# 8_USB_Hub.net
KiCad netlist of a schematic drawn in Altium Designer
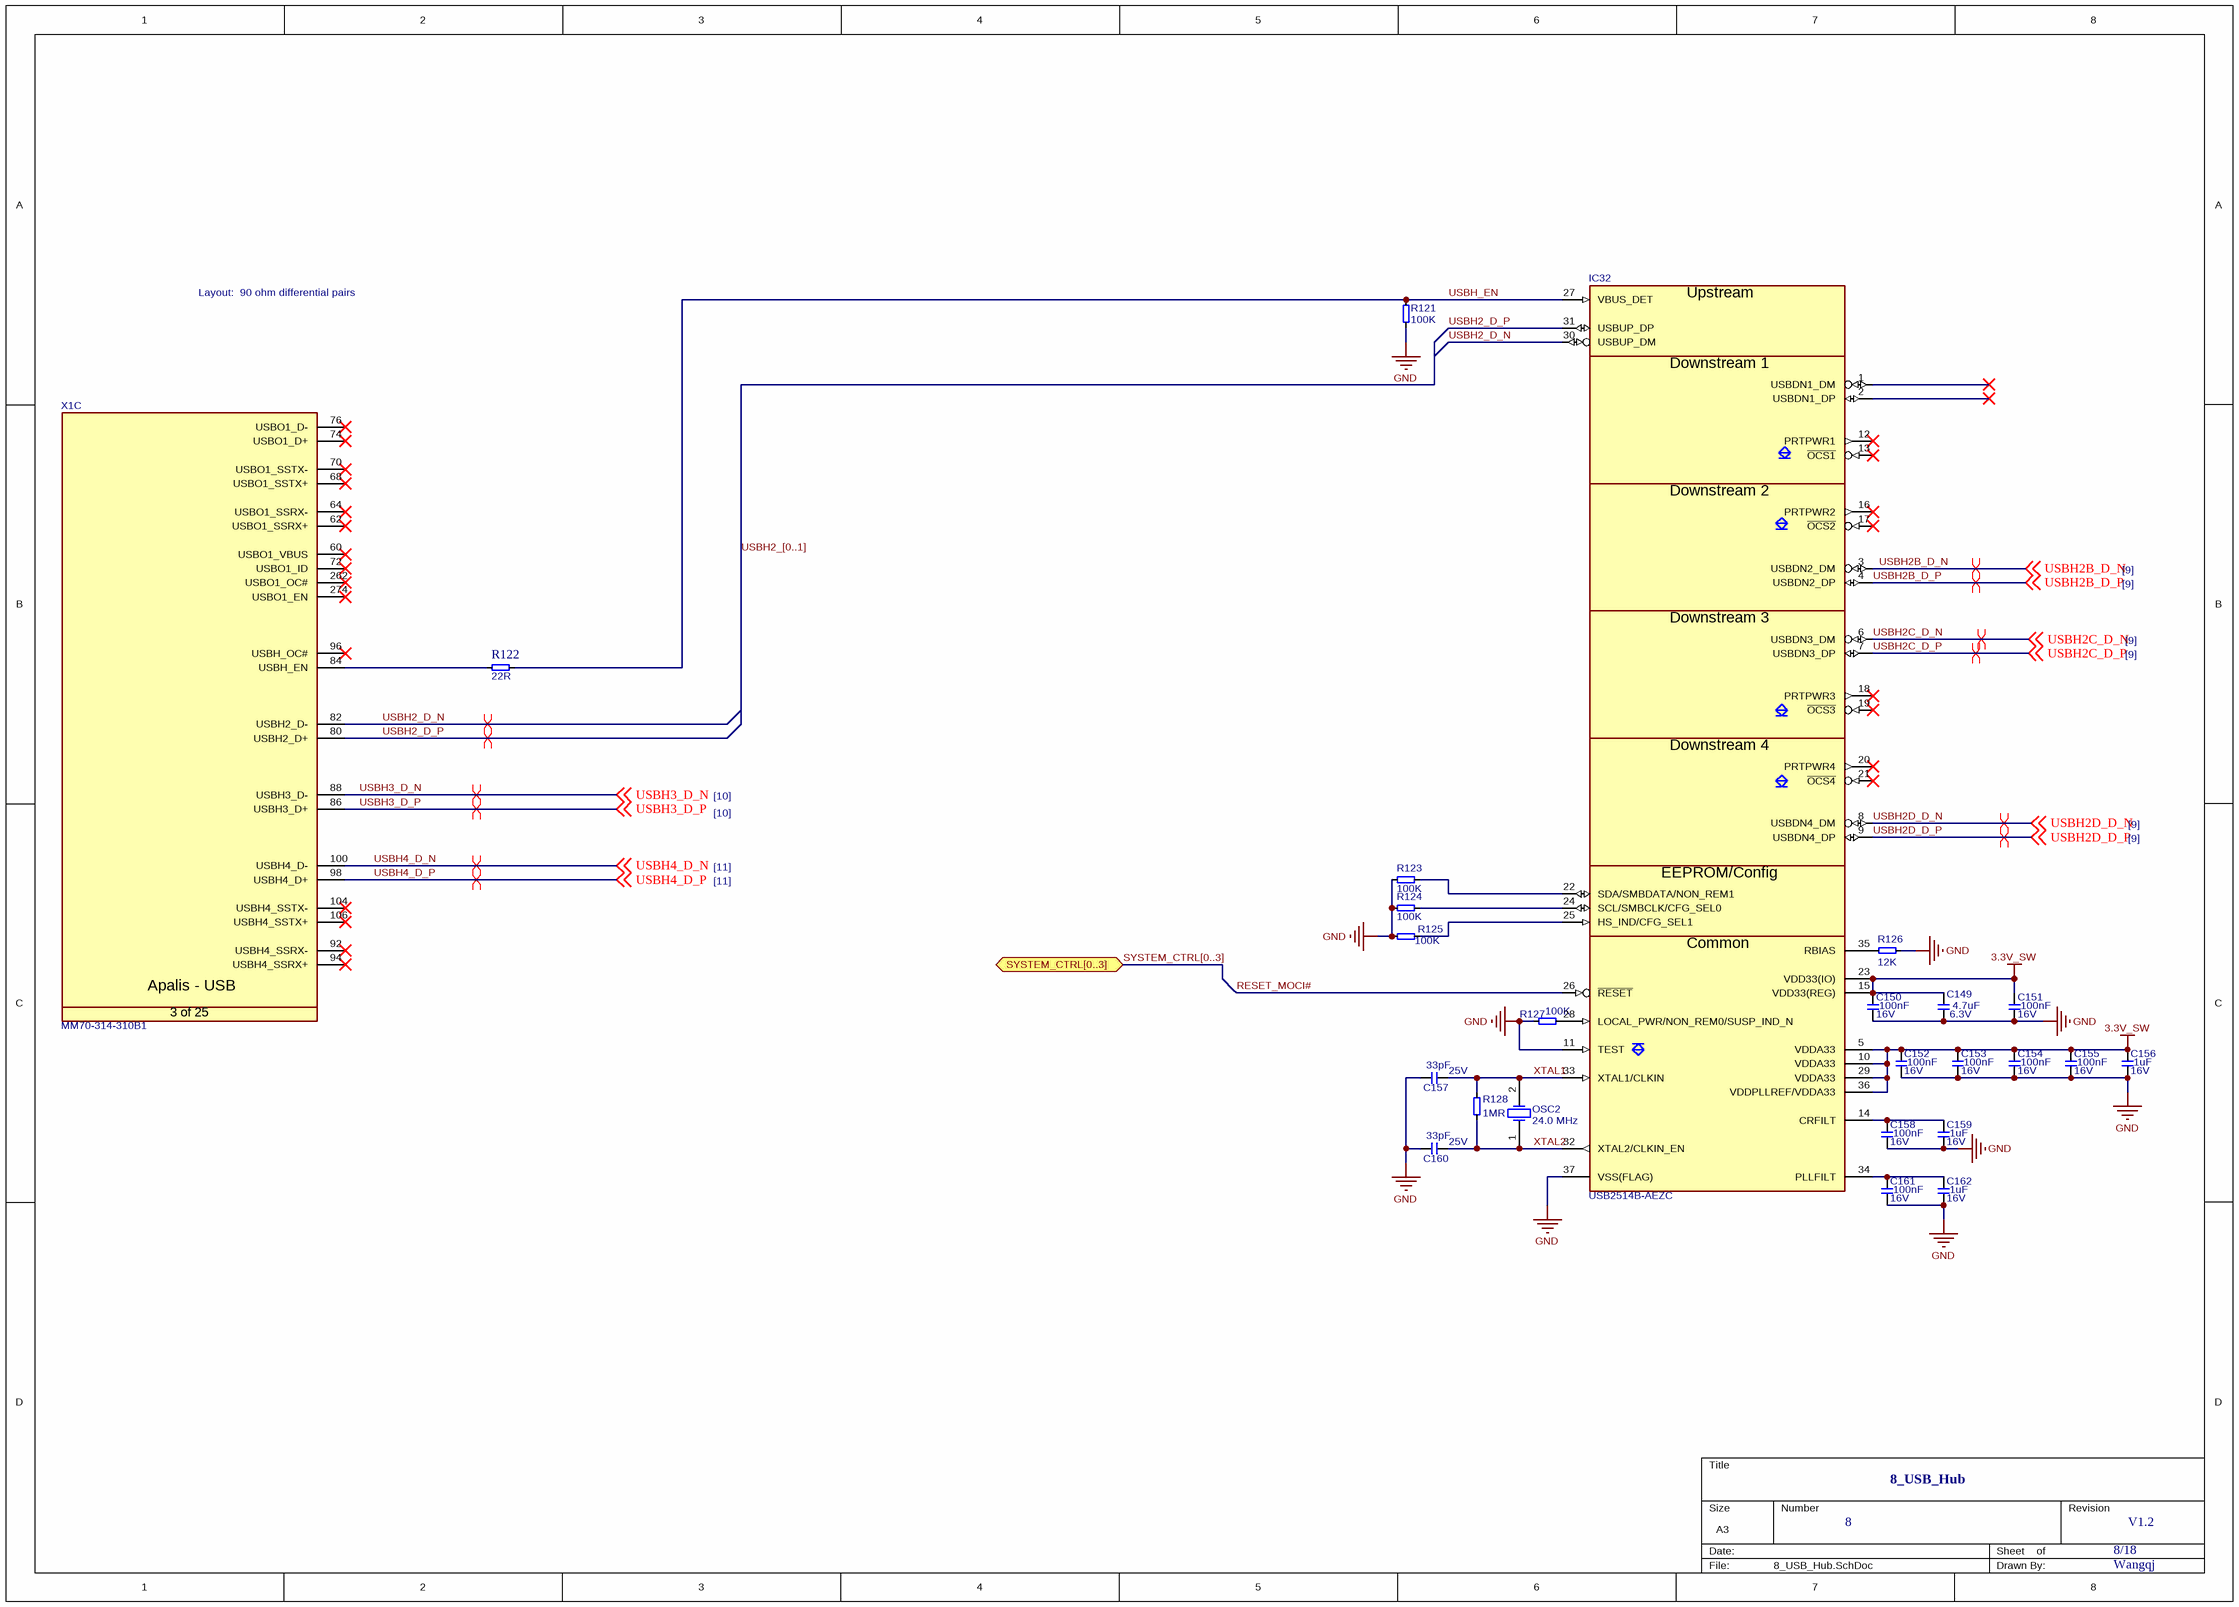
[diagram p0: 8_USB_Hub.SchDoc]

(export (version "E")
  (design (tool "Eeschema 10.0.6"))
  (components
    (comp (ref "C149")
      (value "4.7uF")
      (footprint "T_CAPC0603X33N")
      (description "Capacitor Ceramic X5R 4.7uF 6.3V 20% 0603")
      (fields (field (name "TOLERANCE") "20%") (field (name "RATING") "6.3V"))
      (libsource (lib "Apalis Evaluation Board") (part "C-X5R-4.7uF-6.3V-20%-0603"))
    )
    (comp (ref "C150")
      (value "100nF")
      (footprint "T_CAPC0603X33N")
      (description "Capacitor Ceramic X7R 100nF 16V 10% 0603")
      (fields (field (name "TOLERANCE") "10%") (field (name "RATING") "16V"))
      (libsource (lib "Apalis Evaluation Board") (part "C-X7R-100nF-16V-10%-0603"))
    )
    (comp (ref "C151")
      (value "100nF")
      (footprint "T_CAPC0603X33N")
      (description "Capacitor Ceramic X7R 100nF 16V 10% 0603")
      (fields (field (name "TOLERANCE") "10%") (field (name "RATING") "16V"))
      (libsource (lib "Apalis Evaluation Board") (part "C-X7R-100nF-16V-10%-0603"))
    )
    (comp (ref "C152")
      (value "100nF")
      (footprint "T_CAPC0603X33N")
      (description "Capacitor Ceramic X7R 100nF 16V 10% 0603")
      (fields (field (name "TOLERANCE") "10%") (field (name "RATING") "16V"))
      (libsource (lib "Apalis Evaluation Board") (part "C-X7R-100nF-16V-10%-0603"))
    )
    (comp (ref "C153")
      (value "100nF")
      (footprint "T_CAPC0603X33N")
      (description "Capacitor Ceramic X7R 100nF 16V 10% 0603")
      (fields (field (name "TOLERANCE") "10%") (field (name "RATING") "16V"))
      (libsource (lib "Apalis Evaluation Board") (part "C-X7R-100nF-16V-10%-0603"))
    )
    (comp (ref "C154")
      (value "100nF")
      (footprint "T_CAPC0603X33N")
      (description "Capacitor Ceramic X7R 100nF 16V 10% 0603")
      (fields (field (name "TOLERANCE") "10%") (field (name "RATING") "16V"))
      (libsource (lib "Apalis Evaluation Board") (part "C-X7R-100nF-16V-10%-0603"))
    )
    (comp (ref "C155")
      (value "100nF")
      (footprint "T_CAPC0603X33N")
      (description "Capacitor Ceramic X7R 100nF 16V 10% 0603")
      (fields (field (name "TOLERANCE") "10%") (field (name "RATING") "16V"))
      (libsource (lib "Apalis Evaluation Board") (part "C-X7R-100nF-16V-10%-0603"))
    )
    (comp (ref "C156")
      (value "1uF")
      (footprint "T_CAPC0603X33N")
      (description "Capacitor Ceramic X5R 1uF 16V 20% 0603")
      (fields (field (name "TOLERANCE") "20%") (field (name "RATING") "16V"))
      (libsource (lib "Apalis Evaluation Board") (part "C-X5R-1uF-16V-20%-0603"))
    )
    (comp (ref "C157")
      (value "33pF")
      (footprint "T_CAPC0603X33N")
      (description "Capacitor Ceramic NP0 33pF 25V 10% 0603")
      (fields (field (name "TOLERANCE") "10%") (field (name "RATING") "25V"))
      (libsource (lib "Apalis Evaluation Board") (part "C-NP0-33pF-25V-10%-0603"))
    )
    (comp (ref "C158")
      (value "100nF")
      (footprint "T_CAPC0603X33N")
      (description "Capacitor Ceramic X7R 100nF 16V 10% 0603")
      (fields (field (name "TOLERANCE") "10%") (field (name "RATING") "16V"))
      (libsource (lib "Apalis Evaluation Board") (part "C-X7R-100nF-16V-10%-0603"))
    )
    (comp (ref "C159")
      (value "1uF")
      (footprint "T_CAPC0603X33N")
      (description "Capacitor Ceramic X5R 1uF 16V 20% 0603")
      (fields (field (name "TOLERANCE") "20%") (field (name "RATING") "16V"))
      (libsource (lib "Apalis Evaluation Board") (part "C-X5R-1uF-16V-20%-0603"))
    )
    (comp (ref "C160")
      (value "33pF")
      (footprint "T_CAPC0603X33N")
      (description "Capacitor Ceramic NP0 33pF 25V 10% 0603")
      (fields (field (name "TOLERANCE") "10%") (field (name "RATING") "25V"))
      (libsource (lib "Apalis Evaluation Board") (part "C-NP0-33pF-25V-10%-0603"))
    )
    (comp (ref "C161")
      (value "100nF")
      (footprint "T_CAPC0603X33N")
      (description "Capacitor Ceramic X7R 100nF 16V 10% 0603")
      (fields (field (name "TOLERANCE") "10%") (field (name "RATING") "16V"))
      (libsource (lib "Apalis Evaluation Board") (part "C-X7R-100nF-16V-10%-0603"))
    )
    (comp (ref "C162")
      (value "1uF")
      (footprint "T_CAPC0603X33N")
      (description "Capacitor Ceramic X5R 1uF 16V 20% 0603")
      (fields (field (name "TOLERANCE") "20%") (field (name "RATING") "16V"))
      (libsource (lib "Apalis Evaluation Board") (part "C-X5R-1uF-16V-20%-0603"))
    )
    (comp (ref "IC32")
      (value "USB2514B")
      (footprint "T_SMSC_USB2514B-AEZC")
      (description "4 Port USB HUB")
      (fields (field (name "MANUFACTURER PART NO.") "USB2514B-AEZC"))
      (libsource (lib "Apalis Evaluation Board") (part "IC-SMSC-USB2514B-AEZC"))
    )
    (comp (ref "OSC2")
      (value "24.0 MHz")
      (footprint "Apalis Evaluation Board:SMD-5032_2P")
      (description "Quartz 24.0 MHz")
      (fields
        (field (name "TOLERANCE") "30ppm")
        (field (name "MANUFACTURER PART NO.") "HEX24-24000MHz-18-50R-F-H2-T2-W2-T")
      )
      (libsource (lib "Apalis Evaluation Board") (part "OSC-HORIZON-HEX24-24000MHz-18-50R-F-H2-T2-W2-T"))
    )
    (comp (ref "R121")
      (value "100K")
      (footprint "T_RESC0603X30N")
      (description "Resistor 100 Kohm 63mW 5% 0603")
      (fields (field (name "TOLERANCE") "5%"))
      (libsource (lib "Apalis Evaluation Board") (part "R-100KR-63mW-5%-0603"))
    )
    (comp (ref "R122")
      (value "22R")
      (footprint "T_RESC0603X30N")
      (description "Resistor 22 ohm 63mW 5% 0603")
      (fields (field (name "TOLERANCE") "5%"))
      (libsource (lib "Apalis Evaluation Board") (part "R-22R-63mW-5%-0603"))
    )
    (comp (ref "R123")
      (value "100K")
      (footprint "T_RESC0603X30N")
      (description "Resistor 100 Kohm 63mW 5% 0603")
      (fields (field (name "TOLERANCE") "5%"))
      (libsource (lib "Apalis Evaluation Board") (part "R-100KR-63mW-5%-0603"))
    )
    (comp (ref "R124")
      (value "100K")
      (footprint "T_RESC0603X30N")
      (description "Resistor 100 Kohm 63mW 5% 0603")
      (fields (field (name "TOLERANCE") "5%"))
      (libsource (lib "Apalis Evaluation Board") (part "R-100KR-63mW-5%-0603"))
    )
    (comp (ref "R125")
      (value "100K")
      (footprint "T_RESC0603X30N")
      (description "Resistor 100 Kohm 63mW 5% 0603")
      (fields (field (name "TOLERANCE") "5%"))
      (libsource (lib "Apalis Evaluation Board") (part "R-100KR-63mW-5%-0603"))
    )
    (comp (ref "R126")
      (value "12K")
      (footprint "T_RESC0603X30N")
      (description "Resistor 12 Kohm 63mW 1% 0603")
      (fields (field (name "TOLERANCE") "1%"))
      (libsource (lib "Apalis Evaluation Board") (part "R-12KR-63mW-1%-0603"))
    )
    (comp (ref "R127")
      (value "100K")
      (footprint "T_RESC0603X30N")
      (description "Resistor 100 Kohm 63mW 5% 0603")
      (fields (field (name "TOLERANCE") "5%"))
      (libsource (lib "Apalis Evaluation Board") (part "R-100KR-63mW-5%-0603"))
    )
    (comp (ref "R128")
      (value "1MR")
      (footprint "T_RESC0603X30N")
      (description "Resistor 1Mohm 63mW 5% 0603")
      (fields (field (name "TOLERANCE") "5%"))
      (libsource (lib "Apalis Evaluation Board") (part "R-1MR-63mW-5%-0603"))
    )
    (comp (ref "X1")
      (value "CON-JAE-MM70-314-310B1-314-0.5mm")
      (footprint "T_JAE_MM70-314-310B1")
      (description "MXM3 Connector")
      (fields (field (name "MANUFACTURER PART NO.") "MM70-314-310B1"))
      (libsource (lib "Apalis Evaluation Board") (part "CON-JAE-MM70-314-310B1-314-0.5mm"))
    )
  )
  (nets
    (net (code "7") (name "/RESET_MOCI#") (class "Default")
      (node (ref "IC32") (pin "26") (pinfunction "~{RESET}_26") (pintype "input"))
    )
    (net (code "9") (name "/USBH2_D_N") (class "Default")
      (node (ref "IC32") (pin "30") (pinfunction "USBUP_DM_30") (pintype "bidirectional"))
      (node (ref "X1") (pin "82") (pinfunction "USBH2_D-_82") (pintype "passive"))
    )
    (net (code "10") (name "/USBH2_D_P") (class "Default")
      (node (ref "IC32") (pin "31") (pinfunction "USBUP_DP_31") (pintype "bidirectional"))
      (node (ref "X1") (pin "80") (pinfunction "USBH2_D+_80") (pintype "passive"))
    )
    (net (code "13") (name "/USBH_EN") (class "Default")
      (node (ref "IC32") (pin "27") (pinfunction "VBUS_DET_27") (pintype "input"))
      (node (ref "R121") (pin "2") (pinfunction "2_2") (pintype "passive"))
      (node (ref "R122") (pin "2") (pinfunction "2_2") (pintype "passive"))
    )
    (net (code "14") (name "/XTAL1") (class "Default")
      (node (ref "C157") (pin "2") (pinfunction "2_2") (pintype "passive"))
      (node (ref "IC32") (pin "33") (pinfunction "XTAL1/CLKIN_33") (pintype "input"))
      (node (ref "OSC2") (pin "2") (pinfunction "OSC2_2") (pintype "passive"))
      (node (ref "R128") (pin "2") (pinfunction "2_2") (pintype "passive"))
    )
    (net (code "15") (name "/XTAL2") (class "Default")
      (node (ref "C160") (pin "2") (pinfunction "2_2") (pintype "passive"))
      (node (ref "IC32") (pin "32") (pinfunction "XTAL2/CLKIN_EN_32") (pintype "output"))
      (node (ref "OSC2") (pin "1") (pinfunction "OSC1_1") (pintype "passive"))
      (node (ref "R128") (pin "1") (pinfunction "1_1") (pintype "passive"))
    )
    (net (code "16") (name "3.3V_SW") (class "Default")
      (node (ref "C149") (pin "2") (pinfunction "2_2") (pintype "passive"))
      (node (ref "C150") (pin "2") (pinfunction "2_2") (pintype "passive"))
      (node (ref "C151") (pin "2") (pinfunction "2_2") (pintype "passive"))
      (node (ref "C152") (pin "2") (pinfunction "2_2") (pintype "passive"))
      (node (ref "C153") (pin "2") (pinfunction "2_2") (pintype "passive"))
      (node (ref "C154") (pin "2") (pinfunction "2_2") (pintype "passive"))
      (node (ref "C155") (pin "2") (pinfunction "2_2") (pintype "passive"))
      (node (ref "C156") (pin "2") (pinfunction "2_2") (pintype "passive"))
      (node (ref "IC32") (pin "10") (pinfunction "VDDA33_10") (pintype "power_in"))
      (node (ref "IC32") (pin "15") (pinfunction "VDD33(REG)_15") (pintype "power_in"))
      (node (ref "IC32") (pin "23") (pinfunction "VDD33(IO)_23") (pintype "power_in"))
      (node (ref "IC32") (pin "29") (pinfunction "VDDA33_29") (pintype "power_in"))
      (node (ref "IC32") (pin "36") (pinfunction "VDDPLLREF/VDDA33_36") (pintype "power_in"))
      (node (ref "IC32") (pin "5") (pinfunction "VDDA33_5") (pintype "power_in"))
    )
    (net (code "17") (name "GND") (class "Default")
      (node (ref "C149") (pin "1") (pinfunction "1_1") (pintype "passive"))
      (node (ref "C150") (pin "1") (pinfunction "1_1") (pintype "passive"))
      (node (ref "C151") (pin "1") (pinfunction "1_1") (pintype "passive"))
      (node (ref "C152") (pin "1") (pinfunction "1_1") (pintype "passive"))
      (node (ref "C153") (pin "1") (pinfunction "1_1") (pintype "passive"))
      (node (ref "C154") (pin "1") (pinfunction "1_1") (pintype "passive"))
      (node (ref "C155") (pin "1") (pinfunction "1_1") (pintype "passive"))
      (node (ref "C156") (pin "1") (pinfunction "1_1") (pintype "passive"))
      (node (ref "C157") (pin "1") (pinfunction "1_1") (pintype "passive"))
      (node (ref "C158") (pin "1") (pinfunction "1_1") (pintype "passive"))
      (node (ref "C159") (pin "1") (pinfunction "1_1") (pintype "passive"))
      (node (ref "C160") (pin "1") (pinfunction "1_1") (pintype "passive"))
      (node (ref "C161") (pin "1") (pinfunction "1_1") (pintype "passive"))
      (node (ref "C162") (pin "1") (pinfunction "1_1") (pintype "passive"))
      (node (ref "IC32") (pin "11") (pinfunction "TEST_11") (pintype "input"))
      (node (ref "IC32") (pin "37") (pinfunction "VSS(FLAG)_37") (pintype "power_in"))
      (node (ref "R121") (pin "1") (pinfunction "1_1") (pintype "passive"))
      (node (ref "R123") (pin "2") (pinfunction "2_2") (pintype "passive"))
      (node (ref "R124") (pin "2") (pinfunction "2_2") (pintype "passive"))
      (node (ref "R125") (pin "2") (pinfunction "2_2") (pintype "passive"))
      (node (ref "R126") (pin "1") (pinfunction "1_1") (pintype "passive"))
      (node (ref "R127") (pin "1") (pinfunction "1_1") (pintype "passive"))
    )
    (net (code "18") (name "Net-(IC32-CRFILT)") (class "Default")
      (node (ref "C158") (pin "2") (pinfunction "2_2") (pintype "passive"))
      (node (ref "C159") (pin "2") (pinfunction "2_2") (pintype "passive"))
      (node (ref "IC32") (pin "14") (pinfunction "CRFILT_14") (pintype "power_in"))
    )
    (net (code "19") (name "Net-(IC32-HS_IND{slash}CFG_SEL1)") (class "Default")
      (node (ref "IC32") (pin "25") (pinfunction "HS_IND/CFG_SEL1_25") (pintype "input"))
      (node (ref "R125") (pin "1") (pinfunction "1_1") (pintype "passive"))
    )
    (net (code "20") (name "Net-(IC32-LOCAL_PWR{slash}NON_REM0{slash}SUSP_IND_N)") (class "Default")
      (node (ref "IC32") (pin "28") (pinfunction "LOCAL_PWR/NON_REM0/SUSP_IND_N_28") (pintype "input"))
      (node (ref "R127") (pin "2") (pinfunction "2_2") (pintype "passive"))
    )
    (net (code "21") (name "Net-(IC32-PLLFILT)") (class "Default")
      (node (ref "C161") (pin "2") (pinfunction "2_2") (pintype "passive"))
      (node (ref "C162") (pin "2") (pinfunction "2_2") (pintype "passive"))
      (node (ref "IC32") (pin "34") (pinfunction "PLLFILT_34") (pintype "power_in"))
    )
    (net (code "22") (name "Net-(IC32-RBIAS)") (class "Default")
      (node (ref "IC32") (pin "35") (pinfunction "RBIAS_35") (pintype "passive"))
      (node (ref "R126") (pin "2") (pinfunction "2_2") (pintype "passive"))
    )
    (net (code "23") (name "Net-(IC32-SCL{slash}SMBCLK{slash}CFG_SEL0)") (class "Default")
      (node (ref "IC32") (pin "24") (pinfunction "SCL/SMBCLK/CFG_SEL0_24") (pintype "bidirectional"))
      (node (ref "R124") (pin "1") (pinfunction "1_1") (pintype "passive"))
    )
    (net (code "24") (name "Net-(IC32-SDA{slash}SMBDATA{slash}NON_REM1)") (class "Default")
      (node (ref "IC32") (pin "22") (pinfunction "SDA/SMBDATA/NON_REM1_22") (pintype "bidirectional"))
      (node (ref "R123") (pin "1") (pinfunction "1_1") (pintype "passive"))
    )
    (net (code "25") (name "Net-(X1C-USBH_EN)") (class "Default")
      (node (ref "R122") (pin "1") (pinfunction "1_1") (pintype "passive"))
      (node (ref "X1") (pin "84") (pinfunction "USBH_EN_84") (pintype "passive"))
    )
    (net (code "26") (name "USBH2B_D_N") (class "Default")
      (node (ref "IC32") (pin "3") (pinfunction "USBDN2_DM_3") (pintype "bidirectional"))
    )
    (net (code "27") (name "USBH2B_D_P") (class "Default")
      (node (ref "IC32") (pin "4") (pinfunction "USBDN2_DP_4") (pintype "bidirectional"))
    )
    (net (code "28") (name "USBH2C_D_N") (class "Default")
      (node (ref "IC32") (pin "6") (pinfunction "USBDN3_DM_6") (pintype "bidirectional"))
    )
    (net (code "29") (name "USBH2C_D_P") (class "Default")
      (node (ref "IC32") (pin "7") (pinfunction "USBDN3_DP_7") (pintype "bidirectional"))
    )
    (net (code "30") (name "USBH2D_D_N") (class "Default")
      (node (ref "IC32") (pin "8") (pinfunction "USBDN4_DM_8") (pintype "bidirectional"))
    )
    (net (code "31") (name "USBH2D_D_P") (class "Default")
      (node (ref "IC32") (pin "9") (pinfunction "USBDN4_DP_9") (pintype "bidirectional"))
    )
    (net (code "32") (name "USBH3_D_N") (class "Default")
      (node (ref "X1") (pin "88") (pinfunction "USBH3_D-_88") (pintype "passive"))
    )
    (net (code "33") (name "USBH3_D_P") (class "Default")
      (node (ref "X1") (pin "86") (pinfunction "USBH3_D+_86") (pintype "passive"))
    )
    (net (code "34") (name "USBH4_D_N") (class "Default")
      (node (ref "X1") (pin "100") (pinfunction "USBH4_D-_100") (pintype "passive"))
    )
    (net (code "35") (name "USBH4_D_P") (class "Default")
      (node (ref "X1") (pin "98") (pinfunction "USBH4_D+_98") (pintype "passive"))
    )
    (net (code "36") (name "unconnected-(IC32-PRTPWR1-Pad12)") (class "Default")
      (node (ref "IC32") (pin "12") (pinfunction "PRTPWR1_12") (pintype "output+no_connect"))
    )
    (net (code "37") (name "unconnected-(IC32-PRTPWR2-Pad16)") (class "Default")
      (node (ref "IC32") (pin "16") (pinfunction "PRTPWR2_16") (pintype "output+no_connect"))
    )
    (net (code "38") (name "unconnected-(IC32-PRTPWR3-Pad18)") (class "Default")
      (node (ref "IC32") (pin "18") (pinfunction "PRTPWR3_18") (pintype "output+no_connect"))
    )
    (net (code "39") (name "unconnected-(IC32-PRTPWR4-Pad20)") (class "Default")
      (node (ref "IC32") (pin "20") (pinfunction "PRTPWR4_20") (pintype "output+no_connect"))
    )
    (net (code "40") (name "unconnected-(IC32-USBDN1_DM-Pad1)") (class "Default")
      (node (ref "IC32") (pin "1") (pinfunction "USBDN1_DM_1") (pintype "bidirectional+no_connect"))
    )
    (net (code "41") (name "unconnected-(IC32-USBDN1_DP-Pad2)") (class "Default")
      (node (ref "IC32") (pin "2") (pinfunction "USBDN1_DP_2") (pintype "bidirectional+no_connect"))
    )
    (net (code "42") (name "unconnected-(IC32-~{OCS1}-Pad13)") (class "Default")
      (node (ref "IC32") (pin "13") (pinfunction "~{OCS1}_13") (pintype "input+no_connect"))
    )
    (net (code "43") (name "unconnected-(IC32-~{OCS2}-Pad17)") (class "Default")
      (node (ref "IC32") (pin "17") (pinfunction "~{OCS2}_17") (pintype "input+no_connect"))
    )
    (net (code "44") (name "unconnected-(IC32-~{OCS3}-Pad19)") (class "Default")
      (node (ref "IC32") (pin "19") (pinfunction "~{OCS3}_19") (pintype "input+no_connect"))
    )
    (net (code "45") (name "unconnected-(IC32-~{OCS4}-Pad21)") (class "Default")
      (node (ref "IC32") (pin "21") (pinfunction "~{OCS4}_21") (pintype "input+no_connect"))
    )
    (net (code "46") (name "unconnected-(X1C-USBH4_SSRX+-Pad94)") (class "Default")
      (node (ref "X1") (pin "94") (pinfunction "USBH4_SSRX+_94") (pintype "passive+no_connect"))
    )
    (net (code "47") (name "unconnected-(X1C-USBH4_SSRX--Pad92)") (class "Default")
      (node (ref "X1") (pin "92") (pinfunction "USBH4_SSRX-_92") (pintype "passive+no_connect"))
    )
    (net (code "48") (name "unconnected-(X1C-USBH4_SSTX+-Pad106)") (class "Default")
      (node (ref "X1") (pin "106") (pinfunction "USBH4_SSTX+_106") (pintype "passive+no_connect"))
    )
    (net (code "49") (name "unconnected-(X1C-USBH4_SSTX--Pad104)") (class "Default")
      (node (ref "X1") (pin "104") (pinfunction "USBH4_SSTX-_104") (pintype "passive+no_connect"))
    )
    (net (code "50") (name "unconnected-(X1C-USBH_OC#-Pad96)") (class "Default")
      (node (ref "X1") (pin "96") (pinfunction "USBH_OC#_96") (pintype "passive+no_connect"))
    )
    (net (code "51") (name "unconnected-(X1C-USBO1_D+-Pad74)") (class "Default")
      (node (ref "X1") (pin "74") (pinfunction "USBO1_D+_74") (pintype "passive+no_connect"))
    )
    (net (code "52") (name "unconnected-(X1C-USBO1_D--Pad76)") (class "Default")
      (node (ref "X1") (pin "76") (pinfunction "USBO1_D-_76") (pintype "passive+no_connect"))
    )
    (net (code "53") (name "unconnected-(X1C-USBO1_EN-Pad274)") (class "Default")
      (node (ref "X1") (pin "274") (pinfunction "USBO1_EN_274") (pintype "passive+no_connect"))
    )
    (net (code "54") (name "unconnected-(X1C-USBO1_ID-Pad72)") (class "Default")
      (node (ref "X1") (pin "72") (pinfunction "USBO1_ID_72") (pintype "passive+no_connect"))
    )
    (net (code "55") (name "unconnected-(X1C-USBO1_OC#-Pad262)") (class "Default")
      (node (ref "X1") (pin "262") (pinfunction "USBO1_OC#_262") (pintype "passive+no_connect"))
    )
    (net (code "56") (name "unconnected-(X1C-USBO1_SSRX+-Pad62)") (class "Default")
      (node (ref "X1") (pin "62") (pinfunction "USBO1_SSRX+_62") (pintype "passive+no_connect"))
    )
    (net (code "57") (name "unconnected-(X1C-USBO1_SSRX--Pad64)") (class "Default")
      (node (ref "X1") (pin "64") (pinfunction "USBO1_SSRX-_64") (pintype "passive+no_connect"))
    )
    (net (code "58") (name "unconnected-(X1C-USBO1_SSTX+-Pad68)") (class "Default")
      (node (ref "X1") (pin "68") (pinfunction "USBO1_SSTX+_68") (pintype "passive+no_connect"))
    )
    (net (code "59") (name "unconnected-(X1C-USBO1_SSTX--Pad70)") (class "Default")
      (node (ref "X1") (pin "70") (pinfunction "USBO1_SSTX-_70") (pintype "passive+no_connect"))
    )
    (net (code "60") (name "unconnected-(X1C-USBO1_VBUS-Pad60)") (class "Default")
      (node (ref "X1") (pin "60") (pinfunction "USBO1_VBUS_60") (pintype "passive+no_connect"))
    )
  )
)
